# ESP32_GRBL_LASER.net
KiCad netlist of a schematic drawn in Altium Designer
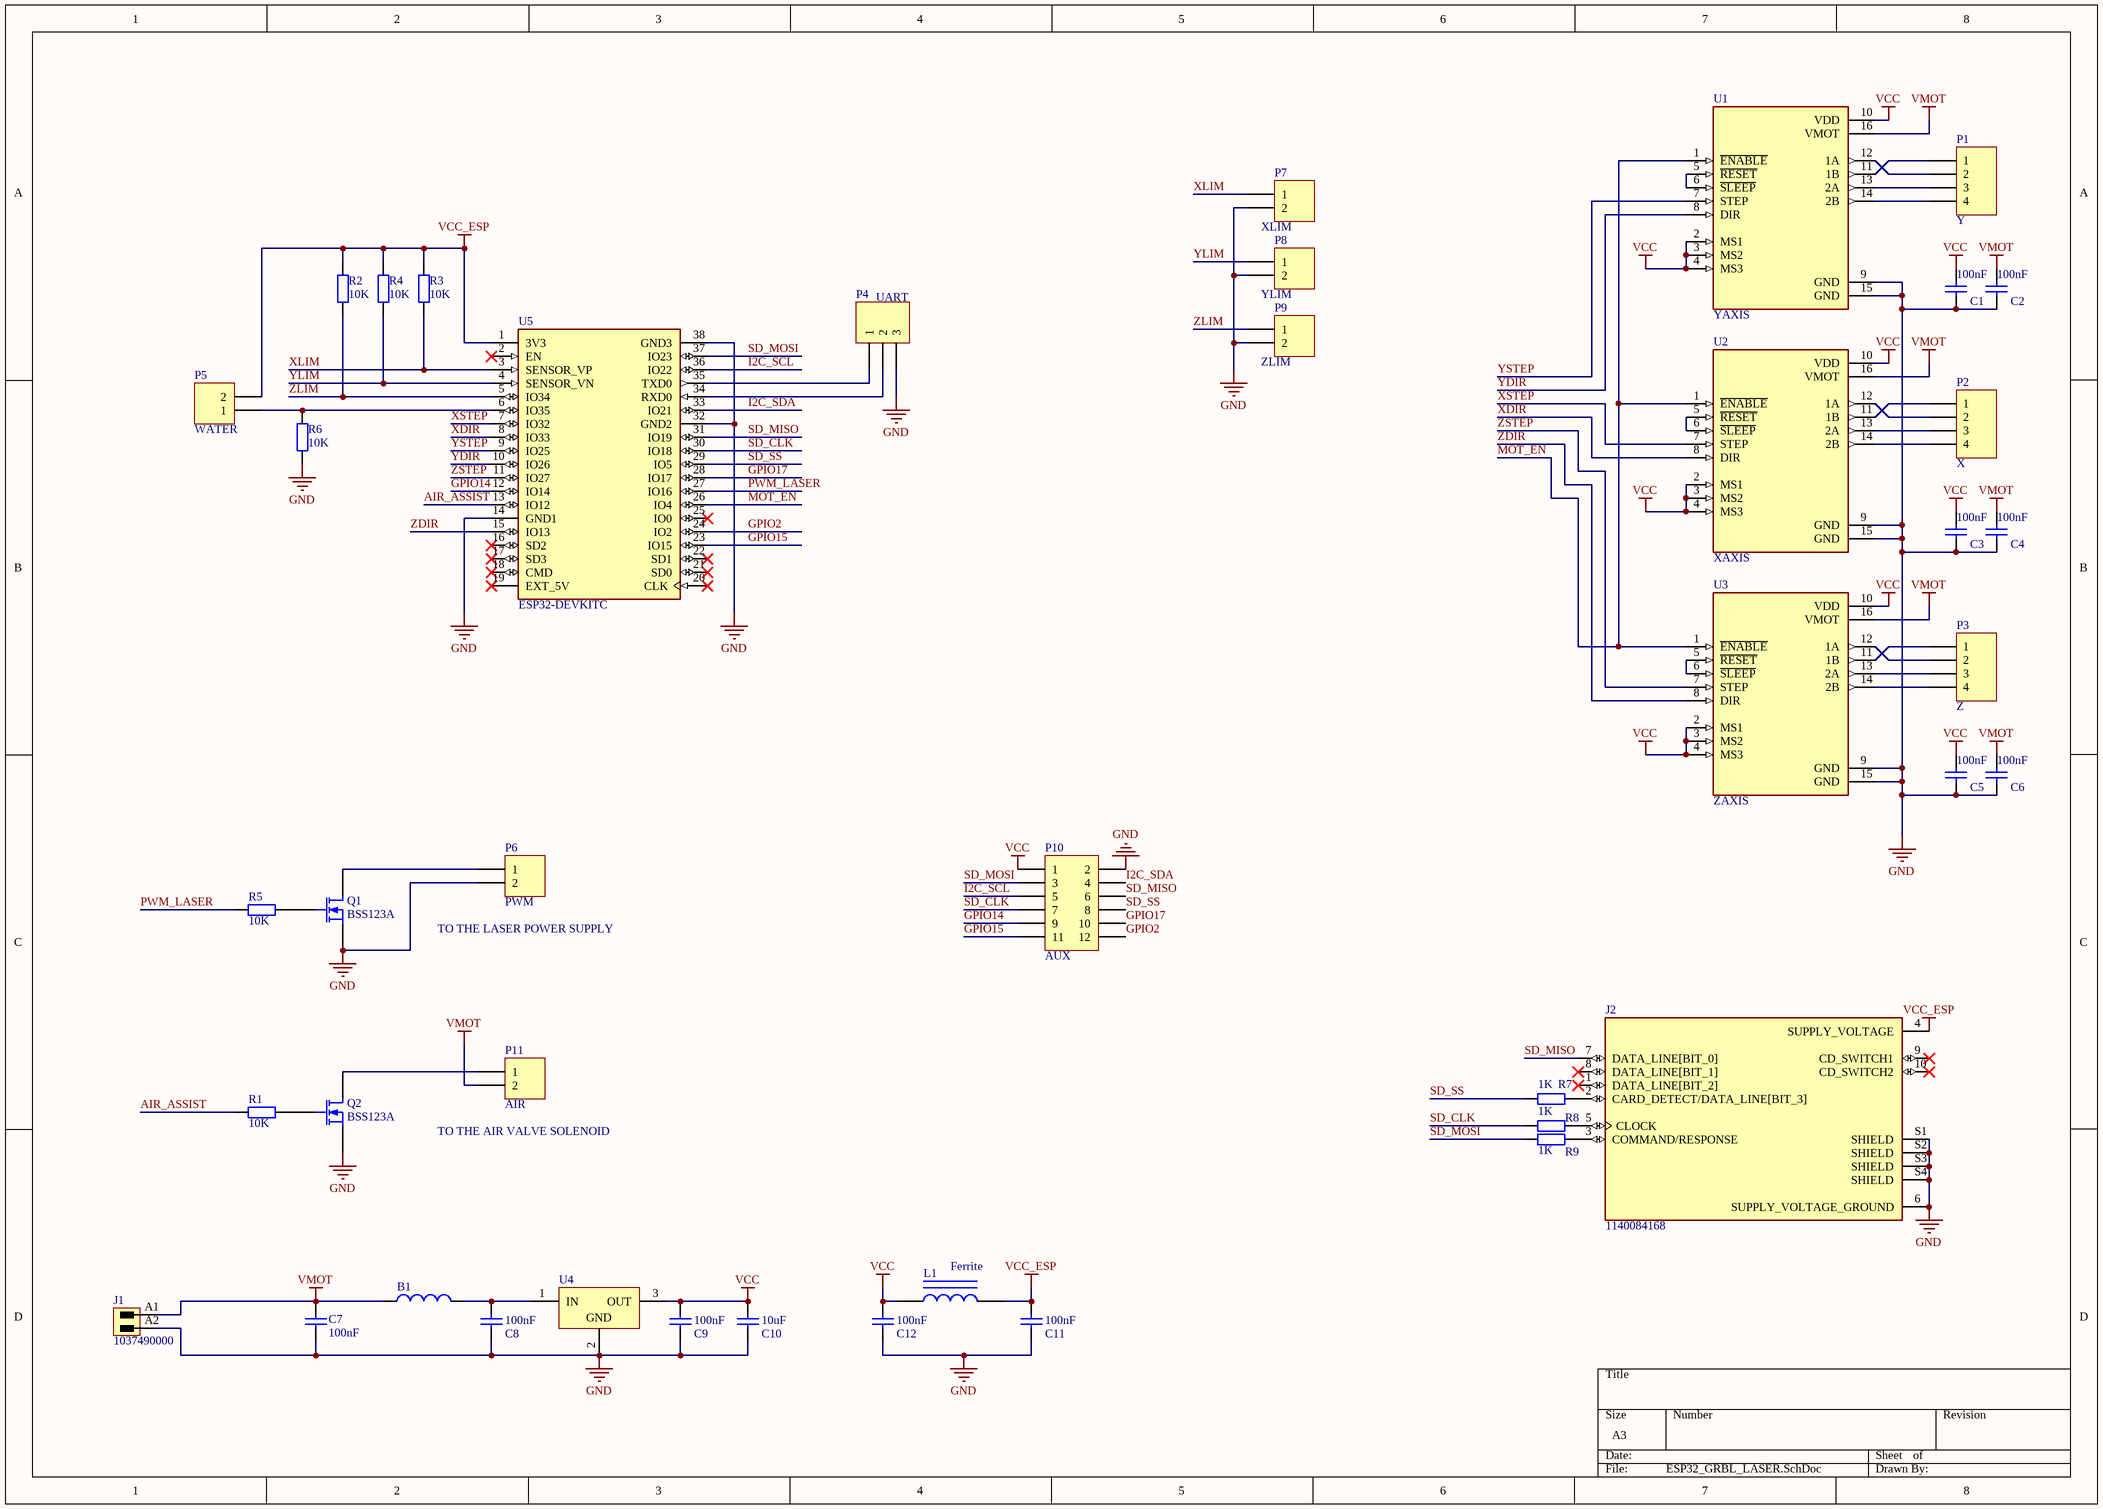
[diagram p0: ESP32_GRBL_LASER.SchDoc]

(export (version "E")
  (design (tool "Eeschema 10.0.6"))
  (components
    (comp (ref "B1")
      (value "Ferrite")
      (footprint "INDC3225N")
      (description "Inductor")
      (fields (field (name "MANUFACTURER") "Murata"))
      (libsource (lib "Miscellaneous Devices") (part "Inductor"))
    )
    (comp (ref "C1")
      (value "100nF")
      (footprint "0805")
      (description "Capacitor (Semiconductor SIM Model)")
      (fields (field (name "VOLTAGE") "50V") (field (name "MANUFACTURER") "Generic Components"))
      (libsource (lib "Miscellaneous Devices") (part "Cap Semi"))
    )
    (comp (ref "C2")
      (value "100nF")
      (footprint "0805")
      (description "Capacitor (Semiconductor SIM Model)")
      (fields (field (name "VOLTAGE") "50V") (field (name "MANUFACTURER") "Generic Components"))
      (libsource (lib "Miscellaneous Devices") (part "Cap Semi"))
    )
    (comp (ref "C3")
      (value "100nF")
      (footprint "0805")
      (description "Capacitor (Semiconductor SIM Model)")
      (fields (field (name "VOLTAGE") "50V") (field (name "MANUFACTURER") "Generic Components"))
      (libsource (lib "Miscellaneous Devices") (part "Cap Semi"))
    )
    (comp (ref "C4")
      (value "100nF")
      (footprint "0805")
      (description "Capacitor (Semiconductor SIM Model)")
      (fields (field (name "VOLTAGE") "50V") (field (name "MANUFACTURER") "Generic Components"))
      (libsource (lib "Miscellaneous Devices") (part "Cap Semi"))
    )
    (comp (ref "C5")
      (value "100nF")
      (footprint "0805")
      (description "Capacitor (Semiconductor SIM Model)")
      (fields (field (name "VOLTAGE") "50V") (field (name "MANUFACTURER") "Generic Components"))
      (libsource (lib "Miscellaneous Devices") (part "Cap Semi"))
    )
    (comp (ref "C6")
      (value "100nF")
      (footprint "0805")
      (description "Capacitor (Semiconductor SIM Model)")
      (fields (field (name "VOLTAGE") "50V") (field (name "MANUFACTURER") "Generic Components"))
      (libsource (lib "Miscellaneous Devices") (part "Cap Semi"))
    )
    (comp (ref "C7")
      (value "100nF")
      (footprint "0805")
      (description "Capacitor (Semiconductor SIM Model)")
      (fields (field (name "VOLTAGE") "50V") (field (name "MANUFACTURER") "Generic Components"))
      (libsource (lib "Miscellaneous Devices") (part "Cap Semi"))
    )
    (comp (ref "C8")
      (value "100nF")
      (footprint "0805")
      (description "Capacitor (Semiconductor SIM Model)")
      (fields (field (name "VOLTAGE") "50V") (field (name "MANUFACTURER") "Generic Components"))
      (libsource (lib "Miscellaneous Devices") (part "Cap Semi"))
    )
    (comp (ref "C9")
      (value "100nF")
      (footprint "0805")
      (description "Capacitor (Semiconductor SIM Model)")
      (fields (field (name "VOLTAGE") "50V") (field (name "MANUFACTURER") "Generic Components"))
      (libsource (lib "Miscellaneous Devices") (part "Cap Semi"))
    )
    (comp (ref "C10")
      (value "10uF")
      (footprint "1210")
      (description "Capacitor (Semiconductor SIM Model)")
      (fields (field (name "VOLTAGE") "25V") (field (name "MANUFACTURER") "Generic Components"))
      (libsource (lib "Miscellaneous Devices") (part "Cap Semi"))
    )
    (comp (ref "C11")
      (value "100nF")
      (footprint "0805")
      (description "Capacitor (Semiconductor SIM Model)")
      (fields (field (name "VOLTAGE") "50V") (field (name "MANUFACTURER") "Generic Components"))
      (libsource (lib "Miscellaneous Devices") (part "Cap Semi"))
    )
    (comp (ref "C12")
      (value "100nF")
      (footprint "0805")
      (description "Capacitor (Semiconductor SIM Model)")
      (fields (field (name "VOLTAGE") "50V") (field (name "MANUFACTURER") "Generic Components"))
      (libsource (lib "Miscellaneous Devices") (part "Cap Semi"))
    )
    (comp (ref "J1")
      (value "1037490000")
      (footprint "SC_3_81_270G_02")
      (description "OMNIMATE Signal - series BC/SC 3.81")
      (fields (field (name "MANUFACTURER") "Weidmueller"))
      (libsource (lib "Weidmueller_OMNIMATE_Signal") (part "1037490000"))
    )
    (comp (ref "J2")
      (value "1140084168")
      (footprint "AMPHENOL_1140084168")
      (description "10 _8 + 2_ Position Card Connector Secure Digital - microSDâ„¢ Surface Mount, Right Angle Gold")
      (fields (field (name "MF") "Amphenol Commercial Products"))
      (libsource (lib "1140084168") (part "1140084168"))
    )
    (comp (ref "L1")
      (value "Ferrite")
      (footprint "INDC2012N")
      (description "Magnetic-Core Inductor")
      (fields (field (name "MANUFACTURER") "Murata"))
      (libsource (lib "Miscellaneous Devices") (part "Inductor Iron"))
    )
    (comp (ref "P1")
      (value "Y")
      (footprint "HDR1X4")
      (description "Header, 4-Pin")
      (fields (field (name "PUBLISHER") "Altium Limited"))
      (libsource (lib "Miscellaneous Connectors") (part "Header 4"))
    )
    (comp (ref "P2")
      (value "X")
      (footprint "HDR1X4")
      (description "Header, 4-Pin")
      (fields (field (name "PUBLISHER") "Altium Limited"))
      (libsource (lib "Miscellaneous Connectors") (part "Header 4"))
    )
    (comp (ref "P3")
      (value "Z")
      (footprint "HDR1X4")
      (description "Header, 4-Pin")
      (fields (field (name "PUBLISHER") "Altium Limited"))
      (libsource (lib "Miscellaneous Connectors") (part "Header 4"))
    )
    (comp (ref "P4")
      (value "UART")
      (footprint "HDR1X3")
      (description "Header, 3-Pin")
      (fields (field (name "PUBLISHER") "Altium Limited"))
      (libsource (lib "Miscellaneous Connectors") (part "Header 3"))
    )
    (comp (ref "P5")
      (value "WATER")
      (footprint "HDR1X2")
      (description "Header, 2-Pin")
      (fields (field (name "PUBLISHER") "Altium Limited"))
      (libsource (lib "") (part "Header 2_1"))
    )
    (comp (ref "P6")
      (value "PWM")
      (footprint "HDR1X2")
      (description "Header, 2-Pin")
      (fields (field (name "PUBLISHER") "Altium Limited"))
      (libsource (lib "Miscellaneous Connectors") (part "Header 2"))
    )
    (comp (ref "P7")
      (value "XLIM")
      (footprint "HDR1X2")
      (description "Header, 2-Pin")
      (fields (field (name "PUBLISHER") "Altium Limited"))
      (libsource (lib "Miscellaneous Connectors") (part "Header 2"))
    )
    (comp (ref "P8")
      (value "YLIM")
      (footprint "HDR1X2")
      (description "Header, 2-Pin")
      (fields (field (name "PUBLISHER") "Altium Limited"))
      (libsource (lib "Miscellaneous Connectors") (part "Header 2"))
    )
    (comp (ref "P9")
      (value "ZLIM")
      (footprint "HDR1X2")
      (description "Header, 2-Pin")
      (fields (field (name "PUBLISHER") "Altium Limited"))
      (libsource (lib "Miscellaneous Connectors") (part "Header 2"))
    )
    (comp (ref "P10")
      (value "AUX")
      (footprint "HDR2X6")
      (description "Header, 6-Pin, Dual row")
      (fields (field (name "PUBLISHER") "Altium Limited"))
      (libsource (lib "Miscellaneous Connectors") (part "Header 6X2"))
    )
    (comp (ref "P11")
      (value "AIR")
      (footprint "HDR1X2")
      (description "Header, 2-Pin")
      (fields (field (name "PUBLISHER") "Altium Limited"))
      (libsource (lib "Miscellaneous Connectors") (part "Header 2"))
    )
    (comp (ref "Q1")
      (value "BSS123A")
      (footprint "SOT23_M")
      (description "N-Channel Enhancement Mode Vertical DMOS FET")
      (fields (field (name "PUBLISHER") "Altium Limited"))
      (libsource (lib "Zetex Discrete MOSFET") (part "BSS123A"))
    )
    (comp (ref "Q2")
      (value "BSS123A")
      (footprint "SOT23_M")
      (description "N-Channel Enhancement Mode Vertical DMOS FET")
      (fields (field (name "PUBLISHER") "Altium Limited"))
      (libsource (lib "Zetex Discrete MOSFET") (part "BSS123A"))
    )
    (comp (ref "R1")
      (value "10K")
      (footprint "0805")
      (description "Resistor")
      (fields (field (name "MANUFACTURER") "Generic Components") (field (name "Comment") "Res2"))
      (libsource (lib "Miscellaneous Devices") (part "Res2"))
    )
    (comp (ref "R2")
      (value "10K")
      (footprint "0805")
      (description "Resistor")
      (fields (field (name "MANUFACTURER") "Generic Components") (field (name "Comment") "Res2"))
      (libsource (lib "") (part "Res2_1"))
    )
    (comp (ref "R3")
      (value "10K")
      (footprint "0805")
      (description "Resistor")
      (fields (field (name "MANUFACTURER") "Generic Components") (field (name "Comment") "Res2"))
      (libsource (lib "") (part "Res2_1"))
    )
    (comp (ref "R4")
      (value "10K")
      (footprint "0805")
      (description "Resistor")
      (fields (field (name "MANUFACTURER") "Generic Components") (field (name "Comment") "Res2"))
      (libsource (lib "") (part "Res2_1"))
    )
    (comp (ref "R5")
      (value "10K")
      (footprint "0805")
      (description "Resistor")
      (fields (field (name "MANUFACTURER") "Generic Components") (field (name "Comment") "Res2"))
      (libsource (lib "Miscellaneous Devices") (part "Res2"))
    )
    (comp (ref "R6")
      (value "10K")
      (footprint "0805")
      (description "Resistor")
      (fields (field (name "MANUFACTURER") "Generic Components") (field (name "Comment") "Res2"))
      (libsource (lib "Miscellaneous Devices") (part "Res2"))
    )
    (comp (ref "R7")
      (value "1K")
      (footprint "0805")
      (description "Resistor")
      (fields (field (name "MANUFACTURER") "Generic Components") (field (name "Comment") "Res2"))
      (libsource (lib "Miscellaneous Devices") (part "Res2"))
    )
    (comp (ref "R8")
      (value "1K")
      (footprint "0805")
      (description "Resistor")
      (fields (field (name "MANUFACTURER") "Generic Components") (field (name "Comment") "Res2"))
      (libsource (lib "Miscellaneous Devices") (part "Res2"))
    )
    (comp (ref "R9")
      (value "1K")
      (footprint "0805")
      (description "Resistor")
      (fields (field (name "MANUFACTURER") "Generic Components") (field (name "Comment") "Res2"))
      (libsource (lib "Miscellaneous Devices") (part "Res2"))
    )
    (comp (ref "U1")
      (value "YAXIS")
      (footprint "MODULE_A4988_STEPPER_MOTOR_DRIVER_CARRIER")
      (description "Stepper Motor Driver")
      (fields (field (name "MP") "A4988 STEPPER MOTOR DRIVER CARRIER") (field (name "MF") "Pololu"))
      (libsource (lib "A4988_STEPPER_MOTOR_DRIVER_CARRIER") (part "A4988_STEPPER_MOTOR_DRIVER_CARRIER"))
    )
    (comp (ref "U2")
      (value "XAXIS")
      (footprint "MODULE_A4988_STEPPER_MOTOR_DRIVER_CARRIER")
      (description "Stepper Motor Driver")
      (fields (field (name "MP") "A4988 STEPPER MOTOR DRIVER CARRIER") (field (name "MF") "Pololu"))
      (libsource (lib "A4988_STEPPER_MOTOR_DRIVER_CARRIER") (part "A4988_STEPPER_MOTOR_DRIVER_CARRIER"))
    )
    (comp (ref "U3")
      (value "ZAXIS")
      (footprint "MODULE_A4988_STEPPER_MOTOR_DRIVER_CARRIER")
      (description "Stepper Motor Driver")
      (fields (field (name "MP") "A4988 STEPPER MOTOR DRIVER CARRIER") (field (name "MF") "Pololu"))
      (libsource (lib "A4988_STEPPER_MOTOR_DRIVER_CARRIER") (part "A4988_STEPPER_MOTOR_DRIVER_CARRIER"))
    )
    (comp (ref "U4")
      (value "3V3REG")
      (footprint "TRS1-24xx")
      (description "Switching Regulator,18-32Vin,3.3Vout 1A")
      (libsource (lib "Medios") (part "TSR1-2433"))
    )
    (comp (ref "U5")
      (value "ESP32-DEVKITC")
      (footprint "MODULE_ESP32-DEVKITC")
      (fields (field (name "MP") "ESP32-DEVKITC-32D-F") (field (name "MF") "Espressif Systems"))
      (libsource (lib "ESP32-DEVKITC") (part "ESP32-DEVKITC"))
    )
  )
  (nets
    (net (code "1") (name "/AIR_ASSIST") (class "Default")
      (node (ref "R1") (pin "1") (pinfunction "1_1") (pintype "passive"))
      (node (ref "U5") (pin "13") (pinfunction "IO12_13") (pintype "bidirectional"))
    )
    (net (code "2") (name "/GPIO2") (class "Default")
      (node (ref "P10") (pin "12") (pinfunction "12_12") (pintype "passive"))
      (node (ref "U5") (pin "24") (pinfunction "IO2_24") (pintype "bidirectional"))
    )
    (net (code "3") (name "/GPIO14") (class "Default")
      (node (ref "P10") (pin "9") (pinfunction "9_9") (pintype "passive"))
      (node (ref "U5") (pin "12") (pinfunction "IO14_12") (pintype "bidirectional"))
    )
    (net (code "4") (name "/GPIO15") (class "Default")
      (node (ref "P10") (pin "11") (pinfunction "11_11") (pintype "passive"))
      (node (ref "U5") (pin "23") (pinfunction "IO15_23") (pintype "bidirectional"))
    )
    (net (code "5") (name "/GPIO17") (class "Default")
      (node (ref "P10") (pin "10") (pinfunction "10_10") (pintype "passive"))
      (node (ref "U5") (pin "28") (pinfunction "IO17_28") (pintype "bidirectional"))
    )
    (net (code "6") (name "/I2C_SCL") (class "Default")
      (node (ref "P10") (pin "5") (pinfunction "5_5") (pintype "passive"))
      (node (ref "U5") (pin "36") (pinfunction "IO22_36") (pintype "bidirectional"))
    )
    (net (code "7") (name "/I2C_SDA") (class "Default")
      (node (ref "P10") (pin "4") (pinfunction "4_4") (pintype "passive"))
      (node (ref "U5") (pin "33") (pinfunction "IO21_33") (pintype "bidirectional"))
    )
    (net (code "8") (name "/MOT_EN") (class "Default")
      (node (ref "U1") (pin "1") (pinfunction "~{ENABLE}_1") (pintype "input"))
      (node (ref "U2") (pin "1") (pinfunction "~{ENABLE}_1") (pintype "input"))
      (node (ref "U3") (pin "1") (pinfunction "~{ENABLE}_1") (pintype "input"))
      (node (ref "U5") (pin "26") (pinfunction "IO4_26") (pintype "bidirectional"))
    )
    (net (code "9") (name "/PWM_LASER") (class "Default")
      (node (ref "R5") (pin "1") (pinfunction "1_1") (pintype "passive"))
      (node (ref "U5") (pin "27") (pinfunction "IO16_27") (pintype "bidirectional"))
    )
    (net (code "10") (name "/SD_CLK") (class "Default")
      (node (ref "P10") (pin "7") (pinfunction "7_7") (pintype "passive"))
      (node (ref "R8") (pin "1") (pinfunction "1_1") (pintype "passive"))
      (node (ref "U5") (pin "30") (pinfunction "IO18_30") (pintype "bidirectional"))
    )
    (net (code "11") (name "/SD_MISO") (class "Default")
      (node (ref "J2") (pin "7") (pinfunction "DATA_LINE[BIT_0]_7") (pintype "bidirectional"))
      (node (ref "P10") (pin "6") (pinfunction "6_6") (pintype "passive"))
      (node (ref "U5") (pin "31") (pinfunction "IO19_31") (pintype "bidirectional"))
    )
    (net (code "12") (name "/SD_MOSI") (class "Default")
      (node (ref "P10") (pin "3") (pinfunction "3_3") (pintype "passive"))
      (node (ref "R9") (pin "1") (pinfunction "1_1") (pintype "passive"))
      (node (ref "U5") (pin "37") (pinfunction "IO23_37") (pintype "bidirectional"))
    )
    (net (code "13") (name "/SD_SS") (class "Default")
      (node (ref "P10") (pin "8") (pinfunction "8_8") (pintype "passive"))
      (node (ref "R7") (pin "1") (pinfunction "1_1") (pintype "passive"))
      (node (ref "U5") (pin "29") (pinfunction "IO5_29") (pintype "bidirectional"))
    )
    (net (code "14") (name "/XDIR") (class "Default")
      (node (ref "U2") (pin "8") (pinfunction "DIR_8") (pintype "input"))
      (node (ref "U5") (pin "8") (pinfunction "IO33_8") (pintype "bidirectional"))
    )
    (net (code "15") (name "/XLIM") (class "Default")
      (node (ref "P7") (pin "1") (pinfunction "1_1") (pintype "passive"))
      (node (ref "R3") (pin "2") (pinfunction "2_2") (pintype "passive"))
      (node (ref "U5") (pin "3") (pinfunction "SENSOR_VP_3") (pintype "input"))
    )
    (net (code "16") (name "/XSTEP") (class "Default")
      (node (ref "U2") (pin "7") (pinfunction "STEP_7") (pintype "input"))
      (node (ref "U5") (pin "7") (pinfunction "IO32_7") (pintype "bidirectional"))
    )
    (net (code "17") (name "/YDIR") (class "Default")
      (node (ref "U1") (pin "8") (pinfunction "DIR_8") (pintype "input"))
      (node (ref "U5") (pin "10") (pinfunction "IO26_10") (pintype "bidirectional"))
    )
    (net (code "18") (name "/YLIM") (class "Default")
      (node (ref "P8") (pin "1") (pinfunction "1_1") (pintype "passive"))
      (node (ref "R4") (pin "2") (pinfunction "2_2") (pintype "passive"))
      (node (ref "U5") (pin "4") (pinfunction "SENSOR_VN_4") (pintype "input"))
    )
    (net (code "19") (name "/YSTEP") (class "Default")
      (node (ref "U1") (pin "7") (pinfunction "STEP_7") (pintype "input"))
      (node (ref "U5") (pin "9") (pinfunction "IO25_9") (pintype "bidirectional"))
    )
    (net (code "20") (name "/ZDIR") (class "Default")
      (node (ref "U3") (pin "8") (pinfunction "DIR_8") (pintype "input"))
      (node (ref "U5") (pin "15") (pinfunction "IO13_15") (pintype "bidirectional"))
    )
    (net (code "21") (name "/ZLIM") (class "Default")
      (node (ref "P9") (pin "1") (pinfunction "1_1") (pintype "passive"))
      (node (ref "R2") (pin "2") (pinfunction "2_2") (pintype "passive"))
      (node (ref "U5") (pin "5") (pinfunction "IO34_5") (pintype "bidirectional"))
    )
    (net (code "22") (name "/ZSTEP") (class "Default")
      (node (ref "U3") (pin "7") (pinfunction "STEP_7") (pintype "input"))
      (node (ref "U5") (pin "11") (pinfunction "IO27_11") (pintype "bidirectional"))
    )
    (net (code "23") (name "GND") (class "Default")
      (node (ref "C1") (pin "2") (pinfunction "2_2") (pintype "passive"))
      (node (ref "C10") (pin "2") (pinfunction "2_2") (pintype "passive"))
      (node (ref "C11") (pin "2") (pinfunction "2_2") (pintype "passive"))
      (node (ref "C12") (pin "2") (pinfunction "2_2") (pintype "passive"))
      (node (ref "C2") (pin "2") (pinfunction "2_2") (pintype "passive"))
      (node (ref "C3") (pin "2") (pinfunction "2_2") (pintype "passive"))
      (node (ref "C4") (pin "2") (pinfunction "2_2") (pintype "passive"))
      (node (ref "C5") (pin "2") (pinfunction "2_2") (pintype "passive"))
      (node (ref "C6") (pin "2") (pinfunction "2_2") (pintype "passive"))
      (node (ref "C7") (pin "1") (pinfunction "1_1") (pintype "passive"))
      (node (ref "C8") (pin "2") (pinfunction "2_2") (pintype "passive"))
      (node (ref "C9") (pin "2") (pinfunction "2_2") (pintype "passive"))
      (node (ref "J1") (pin "A2") (pinfunction "A2_A2") (pintype "passive"))
      (node (ref "J2") (pin "6") (pinfunction "SUPPLY_VOLTAGE_GROUND_6") (pintype "power_in"))
      (node (ref "J2") (pin "S1") (pinfunction "SHIELD_S1") (pintype "passive"))
      (node (ref "J2") (pin "S2") (pinfunction "SHIELD_S2") (pintype "passive"))
      (node (ref "J2") (pin "S3") (pinfunction "SHIELD_S3") (pintype "passive"))
      (node (ref "J2") (pin "S4") (pinfunction "SHIELD_S4") (pintype "passive"))
      (node (ref "P10") (pin "2") (pinfunction "2_2") (pintype "passive"))
      (node (ref "P4") (pin "3") (pinfunction "3_3") (pintype "passive"))
      (node (ref "P6") (pin "2") (pinfunction "2_2") (pintype "passive"))
      (node (ref "P7") (pin "2") (pinfunction "2_2") (pintype "passive"))
      (node (ref "P8") (pin "2") (pinfunction "2_2") (pintype "passive"))
      (node (ref "P9") (pin "2") (pinfunction "2_2") (pintype "passive"))
      (node (ref "Q1") (pin "2") (pinfunction "S_2") (pintype "passive"))
      (node (ref "Q2") (pin "2") (pinfunction "S_2") (pintype "passive"))
      (node (ref "R6") (pin "1") (pinfunction "1_1") (pintype "passive"))
      (node (ref "U1") (pin "15") (pinfunction "GND_15") (pintype "power_in"))
      (node (ref "U1") (pin "9") (pinfunction "GND_9") (pintype "power_in"))
      (node (ref "U2") (pin "15") (pinfunction "GND_15") (pintype "power_in"))
      (node (ref "U2") (pin "9") (pinfunction "GND_9") (pintype "power_in"))
      (node (ref "U3") (pin "15") (pinfunction "GND_15") (pintype "power_in"))
      (node (ref "U3") (pin "9") (pinfunction "GND_9") (pintype "power_in"))
      (node (ref "U4") (pin "2") (pinfunction "GND_2") (pintype "power_in"))
      (node (ref "U5") (pin "14") (pinfunction "GND1_14") (pintype "power_in"))
      (node (ref "U5") (pin "32") (pinfunction "GND2_32") (pintype "power_in"))
      (node (ref "U5") (pin "38") (pinfunction "GND3_38") (pintype "power_in"))
    )
    (net (code "24") (name "Net-(J2-CARD_DETECT{slash}DATA_LINE[BIT_3])") (class "Default")
      (node (ref "J2") (pin "2") (pinfunction "CARD_DETECT/DATA_LINE[BIT_3]_2") (pintype "bidirectional"))
      (node (ref "R7") (pin "2") (pinfunction "2_2") (pintype "passive"))
    )
    (net (code "25") (name "Net-(J2-CLOCK)") (class "Default")
      (node (ref "J2") (pin "5") (pinfunction "CLOCK_5") (pintype "bidirectional"))
      (node (ref "R8") (pin "2") (pinfunction "2_2") (pintype "passive"))
    )
    (net (code "26") (name "Net-(J2-COMMAND{slash}RESPONSE)") (class "Default")
      (node (ref "J2") (pin "3") (pinfunction "COMMAND/RESPONSE_3") (pintype "bidirectional"))
      (node (ref "R9") (pin "2") (pinfunction "2_2") (pintype "passive"))
    )
    (net (code "27") (name "Net-(Q1-D)") (class "Default")
      (node (ref "P6") (pin "1") (pinfunction "1_1") (pintype "passive"))
      (node (ref "Q1") (pin "1") (pinfunction "D_1") (pintype "passive"))
    )
    (net (code "28") (name "Net-(Q1-G)") (class "Default")
      (node (ref "Q1") (pin "3") (pinfunction "G_3") (pintype "passive"))
      (node (ref "R5") (pin "2") (pinfunction "2_2") (pintype "passive"))
    )
    (net (code "29") (name "Net-(Q2-D)") (class "Default")
      (node (ref "P11") (pin "1") (pinfunction "1_1") (pintype "passive"))
      (node (ref "Q2") (pin "1") (pinfunction "D_1") (pintype "passive"))
    )
    (net (code "30") (name "Net-(Q2-G)") (class "Default")
      (node (ref "Q2") (pin "3") (pinfunction "G_3") (pintype "passive"))
      (node (ref "R1") (pin "2") (pinfunction "2_2") (pintype "passive"))
    )
    (net (code "31") (name "Net-(U1-1A)") (class "Default")
      (node (ref "P1") (pin "2") (pinfunction "2_2") (pintype "passive"))
      (node (ref "U1") (pin "12") (pinfunction "1A_12") (pintype "output"))
    )
    (net (code "32") (name "Net-(U1-1B)") (class "Default")
      (node (ref "P1") (pin "1") (pinfunction "1_1") (pintype "passive"))
      (node (ref "U1") (pin "11") (pinfunction "1B_11") (pintype "output"))
    )
    (net (code "33") (name "Net-(U1-2A)") (class "Default")
      (node (ref "P1") (pin "3") (pinfunction "3_3") (pintype "passive"))
      (node (ref "U1") (pin "13") (pinfunction "2A_13") (pintype "output"))
    )
    (net (code "34") (name "Net-(U1-2B)") (class "Default")
      (node (ref "P1") (pin "4") (pinfunction "4_4") (pintype "passive"))
      (node (ref "U1") (pin "14") (pinfunction "2B_14") (pintype "output"))
    )
    (net (code "35") (name "Net-(U1-~{RESET})") (class "Default")
      (node (ref "U1") (pin "5") (pinfunction "~{RESET}_5") (pintype "input"))
      (node (ref "U1") (pin "6") (pinfunction "~{SLEEP}_6") (pintype "input"))
    )
    (net (code "36") (name "Net-(U2-1A)") (class "Default")
      (node (ref "P2") (pin "2") (pinfunction "2_2") (pintype "passive"))
      (node (ref "U2") (pin "12") (pinfunction "1A_12") (pintype "output"))
    )
    (net (code "37") (name "Net-(U2-1B)") (class "Default")
      (node (ref "P2") (pin "1") (pinfunction "1_1") (pintype "passive"))
      (node (ref "U2") (pin "11") (pinfunction "1B_11") (pintype "output"))
    )
    (net (code "38") (name "Net-(U2-2A)") (class "Default")
      (node (ref "P2") (pin "3") (pinfunction "3_3") (pintype "passive"))
      (node (ref "U2") (pin "13") (pinfunction "2A_13") (pintype "output"))
    )
    (net (code "39") (name "Net-(U2-2B)") (class "Default")
      (node (ref "P2") (pin "4") (pinfunction "4_4") (pintype "passive"))
      (node (ref "U2") (pin "14") (pinfunction "2B_14") (pintype "output"))
    )
    (net (code "40") (name "Net-(U2-~{RESET})") (class "Default")
      (node (ref "U2") (pin "5") (pinfunction "~{RESET}_5") (pintype "input"))
      (node (ref "U2") (pin "6") (pinfunction "~{SLEEP}_6") (pintype "input"))
    )
    (net (code "41") (name "Net-(U3-1A)") (class "Default")
      (node (ref "P3") (pin "2") (pinfunction "2_2") (pintype "passive"))
      (node (ref "U3") (pin "12") (pinfunction "1A_12") (pintype "output"))
    )
    (net (code "42") (name "Net-(U3-1B)") (class "Default")
      (node (ref "P3") (pin "1") (pinfunction "1_1") (pintype "passive"))
      (node (ref "U3") (pin "11") (pinfunction "1B_11") (pintype "output"))
    )
    (net (code "43") (name "Net-(U3-2A)") (class "Default")
      (node (ref "P3") (pin "3") (pinfunction "3_3") (pintype "passive"))
      (node (ref "U3") (pin "13") (pinfunction "2A_13") (pintype "output"))
    )
    (net (code "44") (name "Net-(U3-2B)") (class "Default")
      (node (ref "P3") (pin "4") (pinfunction "4_4") (pintype "passive"))
      (node (ref "U3") (pin "14") (pinfunction "2B_14") (pintype "output"))
    )
    (net (code "45") (name "Net-(U3-~{RESET})") (class "Default")
      (node (ref "U3") (pin "5") (pinfunction "~{RESET}_5") (pintype "input"))
      (node (ref "U3") (pin "6") (pinfunction "~{SLEEP}_6") (pintype "input"))
    )
    (net (code "46") (name "Net-(U4-IN)") (class "Default")
      (node (ref "B1") (pin "2") (pinfunction "2_2") (pintype "passive"))
      (node (ref "C8") (pin "1") (pinfunction "1_1") (pintype "passive"))
      (node (ref "U4") (pin "1") (pinfunction "IN_1") (pintype "power_in"))
    )
    (net (code "47") (name "Net-(U5-IO35)") (class "Default")
      (node (ref "P5") (pin "1") (pinfunction "1_1") (pintype "passive"))
      (node (ref "R6") (pin "2") (pinfunction "2_2") (pintype "passive"))
      (node (ref "U5") (pin "6") (pinfunction "IO35_6") (pintype "bidirectional"))
    )
    (net (code "48") (name "Net-(U5-RXD0)") (class "Default")
      (node (ref "P4") (pin "2") (pinfunction "2_2") (pintype "passive"))
      (node (ref "U5") (pin "34") (pinfunction "RXD0_34") (pintype "input"))
    )
    (net (code "49") (name "Net-(U5-TXD0)") (class "Default")
      (node (ref "P4") (pin "1") (pinfunction "1_1") (pintype "passive"))
      (node (ref "U5") (pin "35") (pinfunction "TXD0_35") (pintype "output"))
    )
    (net (code "50") (name "VCC") (class "Default")
      (node (ref "C1") (pin "1") (pinfunction "1_1") (pintype "passive"))
      (node (ref "C10") (pin "1") (pinfunction "1_1") (pintype "passive"))
      (node (ref "C12") (pin "1") (pinfunction "1_1") (pintype "passive"))
      (node (ref "C3") (pin "1") (pinfunction "1_1") (pintype "passive"))
      (node (ref "C5") (pin "1") (pinfunction "1_1") (pintype "passive"))
      (node (ref "C9") (pin "1") (pinfunction "1_1") (pintype "passive"))
      (node (ref "L1") (pin "1") (pinfunction "1_1") (pintype "passive"))
      (node (ref "P10") (pin "1") (pinfunction "1_1") (pintype "passive"))
      (node (ref "U1") (pin "10") (pinfunction "VDD_10") (pintype "power_in"))
      (node (ref "U1") (pin "2") (pinfunction "MS1_2") (pintype "input"))
      (node (ref "U1") (pin "3") (pinfunction "MS2_3") (pintype "input"))
      (node (ref "U1") (pin "4") (pinfunction "MS3_4") (pintype "input"))
      (node (ref "U2") (pin "10") (pinfunction "VDD_10") (pintype "power_in"))
      (node (ref "U2") (pin "2") (pinfunction "MS1_2") (pintype "input"))
      (node (ref "U2") (pin "3") (pinfunction "MS2_3") (pintype "input"))
      (node (ref "U2") (pin "4") (pinfunction "MS3_4") (pintype "input"))
      (node (ref "U3") (pin "10") (pinfunction "VDD_10") (pintype "power_in"))
      (node (ref "U3") (pin "2") (pinfunction "MS1_2") (pintype "input"))
      (node (ref "U3") (pin "3") (pinfunction "MS2_3") (pintype "input"))
      (node (ref "U3") (pin "4") (pinfunction "MS3_4") (pintype "input"))
      (node (ref "U4") (pin "3") (pinfunction "OUT_3") (pintype "power_in"))
    )
    (net (code "51") (name "VCC_ESP") (class "Default")
      (node (ref "C11") (pin "1") (pinfunction "1_1") (pintype "passive"))
      (node (ref "J2") (pin "4") (pinfunction "SUPPLY_VOLTAGE_4") (pintype "power_in"))
      (node (ref "L1") (pin "2") (pinfunction "2_2") (pintype "passive"))
      (node (ref "P5") (pin "2") (pinfunction "2_2") (pintype "passive"))
      (node (ref "R2") (pin "1") (pinfunction "1_1") (pintype "passive"))
      (node (ref "R3") (pin "1") (pinfunction "1_1") (pintype "passive"))
      (node (ref "R4") (pin "1") (pinfunction "1_1") (pintype "passive"))
      (node (ref "U5") (pin "1") (pinfunction "3V3_1") (pintype "power_in"))
    )
    (net (code "52") (name "VMOT") (class "Default")
      (node (ref "B1") (pin "1") (pinfunction "1_1") (pintype "passive"))
      (node (ref "C2") (pin "1") (pinfunction "1_1") (pintype "passive"))
      (node (ref "C4") (pin "1") (pinfunction "1_1") (pintype "passive"))
      (node (ref "C6") (pin "1") (pinfunction "1_1") (pintype "passive"))
      (node (ref "C7") (pin "2") (pinfunction "2_2") (pintype "passive"))
      (node (ref "J1") (pin "A1") (pinfunction "A1_A1") (pintype "passive"))
      (node (ref "P11") (pin "2") (pinfunction "2_2") (pintype "passive"))
      (node (ref "U1") (pin "16") (pinfunction "VMOT_16") (pintype "power_in"))
      (node (ref "U2") (pin "16") (pinfunction "VMOT_16") (pintype "power_in"))
      (node (ref "U3") (pin "16") (pinfunction "VMOT_16") (pintype "power_in"))
    )
    (net (code "53") (name "unconnected-(J2-CD_SWITCH1-Pad9)") (class "Default")
      (node (ref "J2") (pin "9") (pinfunction "CD_SWITCH1_9") (pintype "bidirectional+no_connect"))
    )
    (net (code "54") (name "unconnected-(J2-CD_SWITCH2-Pad10)") (class "Default")
      (node (ref "J2") (pin "10") (pinfunction "CD_SWITCH2_10") (pintype "bidirectional+no_connect"))
    )
    (net (code "55") (name "unconnected-(J2-DATA_LINE[BIT_1]-Pad8)") (class "Default")
      (node (ref "J2") (pin "8") (pinfunction "DATA_LINE[BIT_1]_8") (pintype "bidirectional+no_connect"))
    )
    (net (code "56") (name "unconnected-(J2-DATA_LINE[BIT_2]-Pad1)") (class "Default")
      (node (ref "J2") (pin "1") (pinfunction "DATA_LINE[BIT_2]_1") (pintype "bidirectional+no_connect"))
    )
    (net (code "57") (name "unconnected-(U5-CLK-Pad20)") (class "Default")
      (node (ref "U5") (pin "20") (pinfunction "CLK_20") (pintype "input+no_connect"))
    )
    (net (code "58") (name "unconnected-(U5-CMD-Pad18)") (class "Default")
      (node (ref "U5") (pin "18") (pinfunction "CMD_18") (pintype "bidirectional+no_connect"))
    )
    (net (code "59") (name "unconnected-(U5-EN-Pad2)") (class "Default")
      (node (ref "U5") (pin "2") (pinfunction "EN_2") (pintype "input+no_connect"))
    )
    (net (code "60") (name "unconnected-(U5-EXT_5V-Pad19)") (class "Default")
      (node (ref "U5") (pin "19") (pinfunction "EXT_5V_19") (pintype "power_in+no_connect"))
    )
    (net (code "61") (name "unconnected-(U5-IO0-Pad25)") (class "Default")
      (node (ref "U5") (pin "25") (pinfunction "IO0_25") (pintype "bidirectional+no_connect"))
    )
    (net (code "62") (name "unconnected-(U5-SD0-Pad21)") (class "Default")
      (node (ref "U5") (pin "21") (pinfunction "SD0_21") (pintype "bidirectional+no_connect"))
    )
    (net (code "63") (name "unconnected-(U5-SD1-Pad22)") (class "Default")
      (node (ref "U5") (pin "22") (pinfunction "SD1_22") (pintype "bidirectional+no_connect"))
    )
    (net (code "64") (name "unconnected-(U5-SD2-Pad16)") (class "Default")
      (node (ref "U5") (pin "16") (pinfunction "SD2_16") (pintype "bidirectional+no_connect"))
    )
    (net (code "65") (name "unconnected-(U5-SD3-Pad17)") (class "Default")
      (node (ref "U5") (pin "17") (pinfunction "SD3_17") (pintype "bidirectional+no_connect"))
    )
  )
)
